# Rev_1.net
KiCad netlist of a schematic drawn in EAGLE
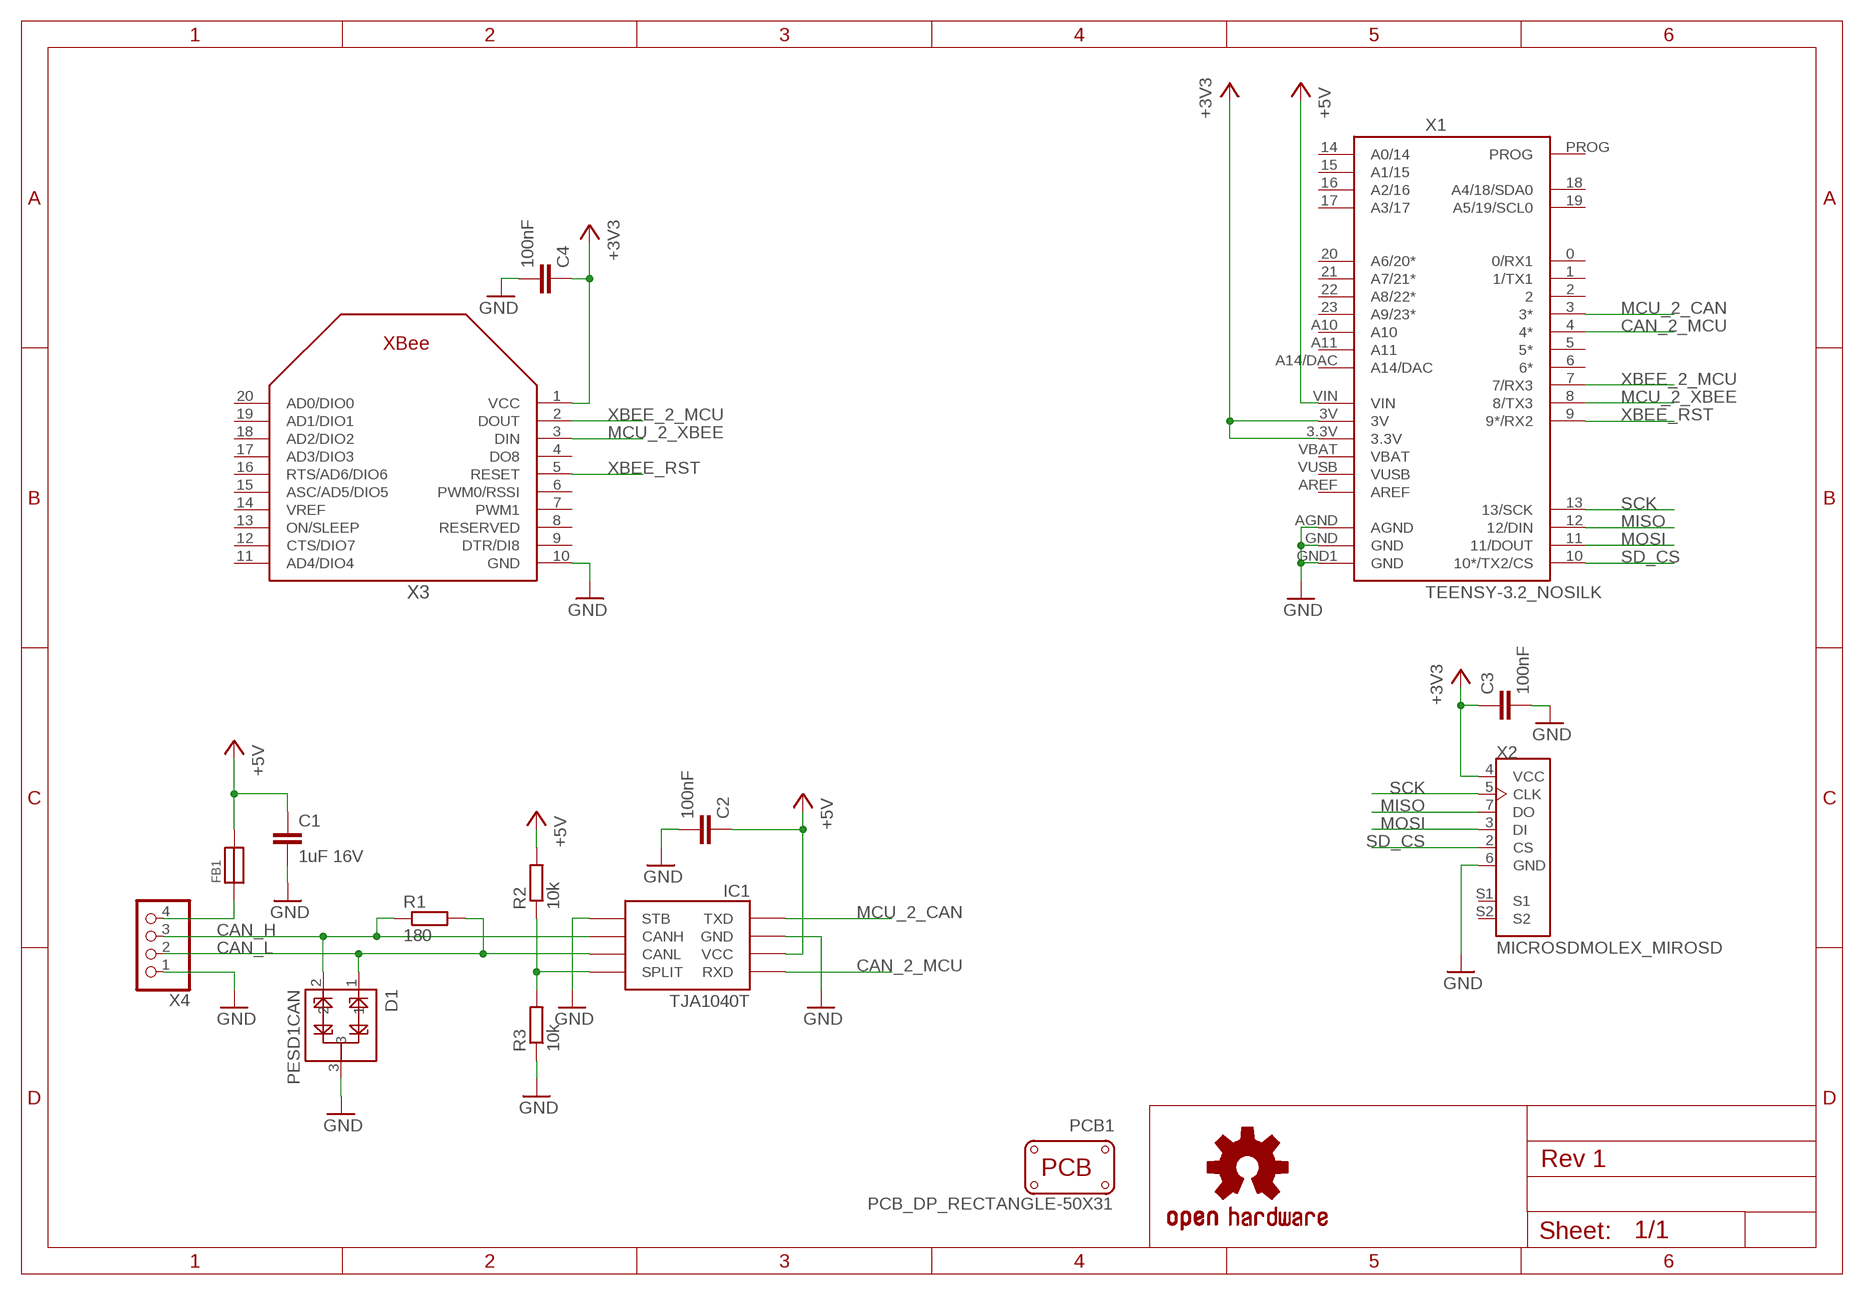
[diagram p0: schematic, sheet 1]

(export (version "E")
  (design (tool "Eeschema 10.0.6"))
  (components
    (comp (ref "C1")
      (value "1uF 16V")
      (footprint "eagle-import:C1206")
      (libsource (lib "eagle-import") (part "C-EUC1206"))
    )
    (comp (ref "C2")
      (value "100nF")
      (footprint "eagle-import:C0603")
      (libsource (lib "eagle-import") (part "C-EUC0603"))
    )
    (comp (ref "C3")
      (value "100nF")
      (footprint "eagle-import:C0603")
      (libsource (lib "eagle-import") (part "C-EUC0603"))
    )
    (comp (ref "C4")
      (value "100nF")
      (footprint "eagle-import:C0603")
      (libsource (lib "eagle-import") (part "C-EUC0603"))
    )
    (comp (ref "D1")
      (value "PESD1CAN")
      (footprint "eagle-import:SOT23-3")
      (libsource (lib "eagle-import") (part "PESD1CAN"))
    )
    (comp (ref "FB1")
      (value "FERRITE")
      (footprint "eagle-import:0603")
      (libsource (lib "eagle-import") (part "FERRITE"))
    )
    (comp (ref "IC1")
      (value "TJA1040T")
      (footprint "eagle-import:SO08")
      (libsource (lib "eagle-import") (part "TJA1040"))
    )
    (comp (ref "LOGO1")
      (value "OSHW-LOGOM")
      (footprint "eagle-import:OSHW-LOGO-M")
      (libsource (lib "eagle-import") (part "OSHW-LOGOM"))
    )
    (comp (ref "PCB1")
      (value "PCB_DP_RECTANGLE-50X31")
      (footprint "eagle-import:DP5031_V1")
      (libsource (lib "eagle-import") (part "PCB_DP_RECTANGLE-50X31"))
    )
    (comp (ref "R1")
      (value "180")
      (footprint "eagle-import:R0603")
      (libsource (lib "eagle-import") (part "R-EU_R0603"))
    )
    (comp (ref "R2")
      (value "10k")
      (footprint "eagle-import:R0603")
      (libsource (lib "eagle-import") (part "R-EU_R0603"))
    )
    (comp (ref "R3")
      (value "10k")
      (footprint "eagle-import:R0603")
      (libsource (lib "eagle-import") (part "R-EU_R0603"))
    )
    (comp (ref "X1")
      (value "TEENSY-3.2_NOSILK")
      (footprint "eagle-import:TEENSY-3.1_NOSILK")
      (libsource (lib "eagle-import") (part "TEENSY-3.1NOSILK"))
    )
    (comp (ref "X2")
      (value "MICROSDMOLEX_MIROSD")
      (footprint "eagle-import:MOLEX_MICROSD")
      (libsource (lib "eagle-import") (part "MICROSDMOLEX_MIROSD"))
    )
    (comp (ref "X3")
      (value "XBEE")
      (footprint "eagle-import:XBEE")
      (libsource (lib "eagle-import") (part "XBEE"))
    )
    (comp (ref "X4")
      (value "JST_4PIN")
      (footprint "eagle-import:JSTPH4")
      (libsource (lib "eagle-import") (part "JST_4PIN"))
    )
  )
  (nets
    (net (code "1") (name "+3V3") (class "Default")
      (node (ref "C3") (pin "1") (pinfunction "1_1") (pintype "passive"))
      (node (ref "C4") (pin "1") (pinfunction "1_1") (pintype "passive"))
      (node (ref "X1") (pin "3.3V") (pinfunction "3.3V_3.3V") (pintype "bidirectional"))
      (node (ref "X1") (pin "3V") (pinfunction "3V_3V") (pintype "bidirectional"))
      (node (ref "X2") (pin "4") (pinfunction "VCC_4") (pintype "passive"))
      (node (ref "X3") (pin "1") (pinfunction "VCC_1") (pintype "power_in"))
    )
    (net (code "2") (name "+5V") (class "Default")
      (node (ref "C1") (pin "1") (pinfunction "1_1") (pintype "passive"))
      (node (ref "C2") (pin "1") (pinfunction "1_1") (pintype "passive"))
      (node (ref "FB1") (pin "2") (pinfunction "P$2_2") (pintype "bidirectional"))
      (node (ref "IC1") (pin "3") (pinfunction "VCC_3") (pintype "bidirectional"))
      (node (ref "R2") (pin "2") (pinfunction "2_2") (pintype "passive"))
      (node (ref "X1") (pin "VIN") (pinfunction "VIN_VIN") (pintype "bidirectional"))
    )
    (net (code "3") (name "/CAN_2_MCU") (class "Default")
      (node (ref "IC1") (pin "4") (pinfunction "RXD_4") (pintype "bidirectional"))
      (node (ref "X1") (pin "4") (pinfunction "4*_4") (pintype "bidirectional"))
    )
    (net (code "4") (name "/CAN_H") (class "Default")
      (node (ref "D1") (pin "2") (pinfunction "2_2") (pintype "bidirectional"))
      (node (ref "IC1") (pin "7") (pinfunction "CANH_7") (pintype "bidirectional"))
      (node (ref "R1") (pin "1") (pinfunction "1_1") (pintype "passive"))
      (node (ref "X4") (pin "3") (pinfunction "3_3") (pintype "passive"))
    )
    (net (code "5") (name "/CAN_L") (class "Default")
      (node (ref "D1") (pin "1") (pinfunction "1_1") (pintype "bidirectional"))
      (node (ref "IC1") (pin "6") (pinfunction "CANL_6") (pintype "bidirectional"))
      (node (ref "R1") (pin "2") (pinfunction "2_2") (pintype "passive"))
      (node (ref "X4") (pin "2") (pinfunction "2_2") (pintype "passive"))
    )
    (net (code "6") (name "/MCU_2_CAN") (class "Default")
      (node (ref "IC1") (pin "1") (pinfunction "TXD_1") (pintype "bidirectional"))
      (node (ref "X1") (pin "3") (pinfunction "3*_3") (pintype "bidirectional"))
    )
    (net (code "7") (name "/MCU_2_XBEE") (class "Default")
      (node (ref "X1") (pin "8") (pinfunction "8/TX3_8") (pintype "bidirectional"))
      (node (ref "X3") (pin "3") (pinfunction "DIN_3") (pintype "input"))
    )
    (net (code "8") (name "/MISO") (class "Default")
      (node (ref "X1") (pin "12") (pinfunction "12/DIN_12") (pintype "bidirectional"))
      (node (ref "X2") (pin "7") (pinfunction "DO_7") (pintype "bidirectional"))
    )
    (net (code "9") (name "/MOSI") (class "Default")
      (node (ref "X1") (pin "11") (pinfunction "11/DOUT_11") (pintype "bidirectional"))
      (node (ref "X2") (pin "3") (pinfunction "DI_3") (pintype "bidirectional"))
    )
    (net (code "10") (name "/SCK") (class "Default")
      (node (ref "X1") (pin "13") (pinfunction "13/SCK_13") (pintype "bidirectional"))
      (node (ref "X2") (pin "5") (pinfunction "CLK_5") (pintype "bidirectional"))
    )
    (net (code "11") (name "/SD_CS") (class "Default")
      (node (ref "X1") (pin "10") (pinfunction "10*/TX2/CS_10") (pintype "bidirectional"))
      (node (ref "X2") (pin "2") (pinfunction "CS_2") (pintype "bidirectional"))
    )
    (net (code "12") (name "/XBEE_2_MCU") (class "Default")
      (node (ref "X1") (pin "7") (pinfunction "7/RX3_7") (pintype "bidirectional"))
      (node (ref "X3") (pin "2") (pinfunction "DOUT_2") (pintype "output"))
    )
    (net (code "13") (name "/XBEE_RST") (class "Default")
      (node (ref "X1") (pin "9") (pinfunction "9*/RX2_9") (pintype "bidirectional"))
      (node (ref "X3") (pin "5") (pinfunction "RESET_5") (pintype "input"))
    )
    (net (code "14") (name "GND") (class "Default")
      (node (ref "C1") (pin "2") (pinfunction "2_2") (pintype "passive"))
      (node (ref "C2") (pin "2") (pinfunction "2_2") (pintype "passive"))
      (node (ref "C3") (pin "2") (pinfunction "2_2") (pintype "passive"))
      (node (ref "C4") (pin "2") (pinfunction "2_2") (pintype "passive"))
      (node (ref "D1") (pin "3") (pinfunction "3_3") (pintype "bidirectional"))
      (node (ref "IC1") (pin "2") (pinfunction "GND_2") (pintype "bidirectional"))
      (node (ref "IC1") (pin "8") (pinfunction "STB_8") (pintype "bidirectional"))
      (node (ref "R3") (pin "1") (pinfunction "1_1") (pintype "passive"))
      (node (ref "X1") (pin "AGND") (pinfunction "AGND_AGND") (pintype "bidirectional"))
      (node (ref "X1") (pin "GND") (pinfunction "GND_GND") (pintype "bidirectional"))
      (node (ref "X1") (pin "GND1") (pinfunction "GND_GND1") (pintype "bidirectional"))
      (node (ref "X2") (pin "6") (pinfunction "GND_6") (pintype "power_in"))
      (node (ref "X3") (pin "10") (pinfunction "GND_10") (pintype "power_in"))
      (node (ref "X4") (pin "1") (pinfunction "1_1") (pintype "passive"))
    )
    (net (code "15") (name "Net-(FB1-P$1)") (class "Default")
      (node (ref "FB1") (pin "1") (pinfunction "P$1_1") (pintype "bidirectional"))
      (node (ref "X4") (pin "4") (pinfunction "4_4") (pintype "passive"))
    )
    (net (code "16") (name "Net-(IC1-SPLIT)") (class "Default")
      (node (ref "IC1") (pin "5") (pinfunction "SPLIT_5") (pintype "bidirectional"))
      (node (ref "R2") (pin "1") (pinfunction "1_1") (pintype "passive"))
      (node (ref "R3") (pin "2") (pinfunction "2_2") (pintype "passive"))
    )
    (net (code "17") (name "unconnected-(X1-0{slash}RX1-Pad0)") (class "Default")
      (node (ref "X1") (pin "0") (pinfunction "0/RX1_0") (pintype "bidirectional"))
    )
    (net (code "18") (name "unconnected-(X1-1{slash}TX1-Pad1)") (class "Default")
      (node (ref "X1") (pin "1") (pinfunction "1/TX1_1") (pintype "bidirectional"))
    )
    (net (code "19") (name "unconnected-(X1-5*-Pad5)") (class "Default")
      (node (ref "X1") (pin "5") (pinfunction "5*_5") (pintype "bidirectional"))
    )
    (net (code "20") (name "unconnected-(X1-6*-Pad6)") (class "Default")
      (node (ref "X1") (pin "6") (pinfunction "6*_6") (pintype "bidirectional"))
    )
    (net (code "21") (name "unconnected-(X1-A0{slash}14-Pad14)") (class "Default")
      (node (ref "X1") (pin "14") (pinfunction "A0/14_14") (pintype "bidirectional"))
    )
    (net (code "22") (name "unconnected-(X1-A1{slash}15-Pad15)") (class "Default")
      (node (ref "X1") (pin "15") (pinfunction "A1/15_15") (pintype "bidirectional"))
    )
    (net (code "23") (name "unconnected-(X1-A2{slash}16-Pad16)") (class "Default")
      (node (ref "X1") (pin "16") (pinfunction "A2/16_16") (pintype "bidirectional"))
    )
    (net (code "24") (name "unconnected-(X1-A3{slash}17-Pad17)") (class "Default")
      (node (ref "X1") (pin "17") (pinfunction "A3/17_17") (pintype "bidirectional"))
    )
    (net (code "25") (name "unconnected-(X1-A4{slash}18{slash}SDA0-Pad18)") (class "Default")
      (node (ref "X1") (pin "18") (pinfunction "A4/18/SDA0_18") (pintype "bidirectional"))
    )
    (net (code "26") (name "unconnected-(X1-A5{slash}19{slash}SCL0-Pad19)") (class "Default")
      (node (ref "X1") (pin "19") (pinfunction "A5/19/SCL0_19") (pintype "bidirectional"))
    )
    (net (code "27") (name "unconnected-(X1-A6{slash}20*-Pad20)") (class "Default")
      (node (ref "X1") (pin "20") (pinfunction "A6/20*_20") (pintype "bidirectional"))
    )
    (net (code "28") (name "unconnected-(X1-A7{slash}21*-Pad21)") (class "Default")
      (node (ref "X1") (pin "21") (pinfunction "A7/21*_21") (pintype "bidirectional"))
    )
    (net (code "29") (name "unconnected-(X1-A8{slash}22*-Pad22)") (class "Default")
      (node (ref "X1") (pin "22") (pinfunction "A8/22*_22") (pintype "bidirectional"))
    )
    (net (code "30") (name "unconnected-(X1-A9{slash}23*-Pad23)") (class "Default")
      (node (ref "X1") (pin "23") (pinfunction "A9/23*_23") (pintype "bidirectional"))
    )
    (net (code "31") (name "unconnected-(X1-Pad2)") (class "Default")
      (node (ref "X1") (pin "2") (pinfunction "2_2") (pintype "bidirectional"))
    )
    (net (code "32") (name "unconnected-(X1-PadA10)") (class "Default")
      (node (ref "X1") (pin "A10") (pinfunction "A10_A10") (pintype "bidirectional"))
    )
    (net (code "33") (name "unconnected-(X1-PadA11)") (class "Default")
      (node (ref "X1") (pin "A11") (pinfunction "A11_A11") (pintype "bidirectional"))
    )
    (net (code "34") (name "unconnected-(X1-PadA14{slash}DAC)") (class "Default")
      (node (ref "X1") (pin "A14/DAC") (pinfunction "A14/DAC_A14/DAC") (pintype "bidirectional"))
    )
    (net (code "35") (name "unconnected-(X1-PadAREF)") (class "Default")
      (node (ref "X1") (pin "AREF") (pinfunction "AREF_AREF") (pintype "bidirectional"))
    )
    (net (code "36") (name "unconnected-(X1-PadPROG)") (class "Default")
      (node (ref "X1") (pin "PROG") (pinfunction "PROG_PROG") (pintype "bidirectional"))
    )
    (net (code "37") (name "unconnected-(X1-PadVBAT)") (class "Default")
      (node (ref "X1") (pin "VBAT") (pinfunction "VBAT_VBAT") (pintype "bidirectional"))
    )
    (net (code "38") (name "unconnected-(X1-PadVUSB)") (class "Default")
      (node (ref "X1") (pin "VUSB") (pinfunction "VUSB_VUSB") (pintype "bidirectional"))
    )
    (net (code "39") (name "unconnected-(X2-PadS1)") (class "Default")
      (node (ref "X2") (pin "S1") (pinfunction "S1_S1") (pintype "bidirectional"))
    )
    (net (code "40") (name "unconnected-(X2-PadS2)") (class "Default")
      (node (ref "X2") (pin "S2") (pinfunction "S2_S2") (pintype "bidirectional"))
    )
    (net (code "41") (name "unconnected-(X3-AD0{slash}DIO0-Pad20)") (class "Default")
      (node (ref "X3") (pin "20") (pinfunction "AD0/DIO0_20") (pintype "bidirectional"))
    )
    (net (code "42") (name "unconnected-(X3-AD1{slash}DIO1-Pad19)") (class "Default")
      (node (ref "X3") (pin "19") (pinfunction "AD1/DIO1_19") (pintype "bidirectional"))
    )
    (net (code "43") (name "unconnected-(X3-AD2{slash}DIO2-Pad18)") (class "Default")
      (node (ref "X3") (pin "18") (pinfunction "AD2/DIO2_18") (pintype "bidirectional"))
    )
    (net (code "44") (name "unconnected-(X3-AD3{slash}DIO3-Pad17)") (class "Default")
      (node (ref "X3") (pin "17") (pinfunction "AD3/DIO3_17") (pintype "bidirectional"))
    )
    (net (code "45") (name "unconnected-(X3-AD4{slash}DIO4-Pad11)") (class "Default")
      (node (ref "X3") (pin "11") (pinfunction "AD4/DIO4_11") (pintype "bidirectional"))
    )
    (net (code "46") (name "unconnected-(X3-ASC{slash}AD5{slash}DIO5-Pad15)") (class "Default")
      (node (ref "X3") (pin "15") (pinfunction "ASC/AD5/DIO5_15") (pintype "bidirectional"))
    )
    (net (code "47") (name "unconnected-(X3-CTS{slash}DIO7-Pad12)") (class "Default")
      (node (ref "X3") (pin "12") (pinfunction "CTS/DIO7_12") (pintype "bidirectional"))
    )
    (net (code "48") (name "unconnected-(X3-DO8-Pad4)") (class "Default")
      (node (ref "X3") (pin "4") (pinfunction "DO8_4") (pintype "output"))
    )
    (net (code "49") (name "unconnected-(X3-DTR{slash}DI8-Pad9)") (class "Default")
      (node (ref "X3") (pin "9") (pinfunction "DTR/DI8_9") (pintype "input"))
    )
    (net (code "50") (name "unconnected-(X3-ON{slash}SLEEP-Pad13)") (class "Default")
      (node (ref "X3") (pin "13") (pinfunction "ON/SLEEP_13") (pintype "output"))
    )
    (net (code "51") (name "unconnected-(X3-PWM0{slash}RSSI-Pad6)") (class "Default")
      (node (ref "X3") (pin "6") (pinfunction "PWM0/RSSI_6") (pintype "output"))
    )
    (net (code "52") (name "unconnected-(X3-PWM1-Pad7)") (class "Default")
      (node (ref "X3") (pin "7") (pinfunction "PWM1_7") (pintype "output"))
    )
    (net (code "53") (name "unconnected-(X3-RESERVED-Pad8)") (class "Default")
      (node (ref "X3") (pin "8") (pinfunction "RESERVED_8") (pintype "no_connect"))
    )
    (net (code "54") (name "unconnected-(X3-RTS{slash}AD6{slash}DIO6-Pad16)") (class "Default")
      (node (ref "X3") (pin "16") (pinfunction "RTS/AD6/DIO6_16") (pintype "bidirectional"))
    )
    (net (code "55") (name "unconnected-(X3-VREF-Pad14)") (class "Default")
      (node (ref "X3") (pin "14") (pinfunction "VREF_14") (pintype "input"))
    )
  )
)
